# UCC.net
KiCad netlist of a schematic drawn in EasyEDA Pro
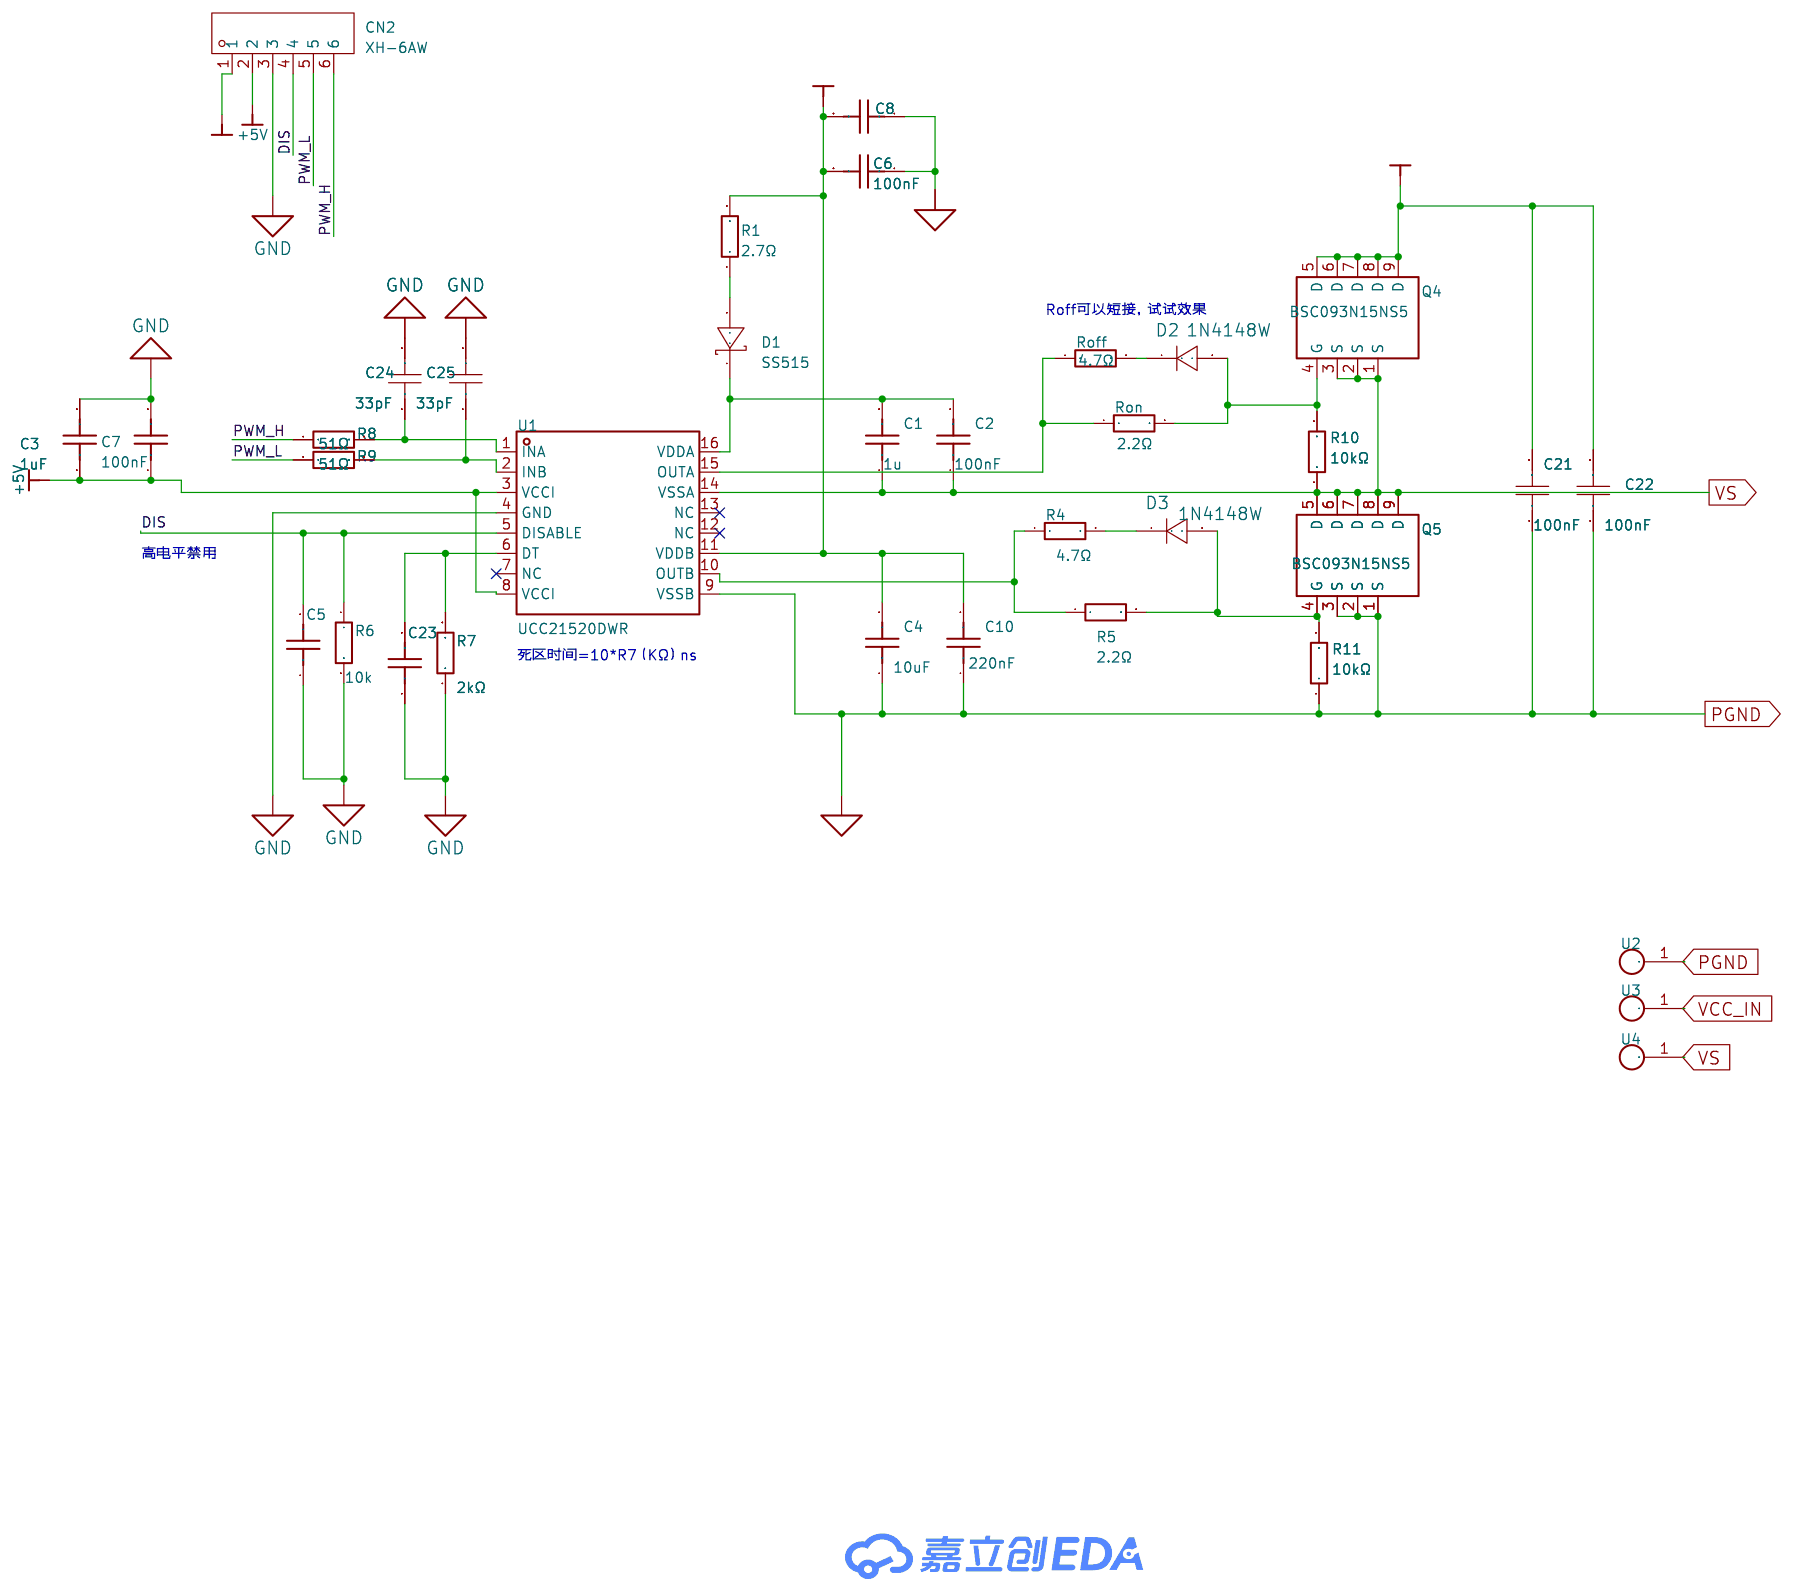
[diagram p0: schematic sheet]

(export (version "E")
  (design (tool "Eeschema 10.0.6"))
  (components
    (comp (ref "C1")
      (value "1u")
      (footprint "easyedapro:C0805")
      (libsource (lib "easyedapro") (part "Capacitance"))
    )
    (comp (ref "C2")
      (value "100nF")
      (footprint "easyedapro:C0805")
      (libsource (lib "easyedapro") (part "Capacitance"))
    )
    (comp (ref "C3")
      (value "1uF")
      (fields
        (field (name "Manufacturer Part") "CC0603KRX7R9BB104")
        (field (name "Manufacturer") "YAGEO(国巨)")
      )
      (libsource (lib "easyedapro") (part "CapAcitance"))
    )
    (comp (ref "C4")
      (value "10uF")
      (fields
        (field (name "Manufacturer Part") "CL10A105KB8NNNC")
        (field (name "Manufacturer") "SAMSUNG(三星)")
      )
      (libsource (lib "easyedapro") (part "CapAcitance"))
    )
    (comp (ref "C5")
      (value "1nF")
      (fields
        (field (name "Manufacturer Part") "CL10B102KB8NNNC")
        (field (name "Manufacturer") "SAMSUNG(三星)")
      )
      (libsource (lib "easyedapro") (part "CapAcitance"))
    )
    (comp (ref "C6")
      (value "100nF")
      (description "容值:1uF;精度:±10%;额定电压:50V;温度系数:X5R;")
      (libsource (lib "easyedapro") (part "CapAcitance"))
    )
    (comp (ref "C7")
      (value "100nF")
      (fields
        (field (name "Manufacturer Part") "CL10A105KB8NNNC")
        (field (name "Manufacturer") "SAMSUNG(三星)")
      )
      (libsource (lib "easyedapro") (part "CapAcitance"))
    )
    (comp (ref "C8")
      (value "10uF")
      (description "容值:10uF;精度:±10%;额定电压:10V;温度系数:X5R;")
      (libsource (lib "easyedapro") (part "CapAcitance"))
    )
    (comp (ref "C10")
      (value "220nF")
      (fields
        (field (name "Manufacturer Part") "CC0603KRX7R9BB104")
        (field (name "Manufacturer") "YAGEO(国巨)")
      )
      (libsource (lib "easyedapro") (part "CapAcitance"))
    )
    (comp (ref "C21")
      (value "100nF")
      (footprint "easyedapro:C1206")
      (description "容值:4.7uF;精度:±10%;额定电压:50V;温度系数:X7R;")
      (fields (field (name "Manufacturer Part") "AM06B475K500NT") (field (name "Manufacturer") "FH(风华)"))
      (libsource (lib "easyedapro") (part "AM06B475K500NT"))
    )
    (comp (ref "C22")
      (value "100nF")
      (footprint "easyedapro:C1206")
      (description "容值:4.7uF;精度:±10%;额定电压:50V;温度系数:X7R;")
      (fields (field (name "Manufacturer Part") "AM06B475K500NT") (field (name "Manufacturer") "FH(风华)"))
      (libsource (lib "easyedapro") (part "AM06B475K500NT"))
    )
    (comp (ref "C23")
      (value "1nF")
      (fields
        (field (name "Manufacturer Part") "CL10B102KB8NNNC")
        (field (name "Manufacturer") "SAMSUNG(三星)")
      )
      (libsource (lib "easyedapro") (part "CapAcitance"))
    )
    (comp (ref "C24")
      (value "33pF")
      (fields
        (field (name "Manufacturer Part") "CC0603JRNPO9BN330")
        (field (name "Manufacturer") "YAGEO(国巨)")
      )
      (libsource (lib "easyedapro") (part "CapAcitance"))
    )
    (comp (ref "C25")
      (value "33pF")
      (fields
        (field (name "Manufacturer Part") "CC0603JRNPO9BN330")
        (field (name "Manufacturer") "YAGEO(国巨)")
      )
      (libsource (lib "easyedapro") (part "CapAcitance"))
    )
    (comp (ref "CN2")
      (value "XH-6AW")
      (footprint "easyedapro:CONN-TH_6P-P2.54_HCTL_XH-6AW_C2908615")
      (fields (field (name "Manufacturer") "HCTL(华灿天禄)"))
      (libsource (lib "easyedapro") (part "XH-6AW_C2908615"))
    )
    (comp (ref "D1")
      (value "SS515")
      (footprint "easyedapro:SMA_L4.3-W2.6-LS5.2-RD")
      (description "100V,5A,VF=0.85V@5A")
      (fields (field (name "Manufacturer") "MDD"))
      (libsource (lib "easyedapro") (part "SS510_C65010"))
    )
    (comp (ref "D2")
      (value "1N4148W")
      (fields (field (name "Manufacturer") "CJ(江苏长电/长晶)"))
      (libsource (lib "easyedapro") (part "1N4148W"))
    )
    (comp (ref "D3")
      (value "1N4148W")
      (fields (field (name "Manufacturer") "CJ(江苏长电/长晶)"))
      (libsource (lib "easyedapro") (part "1N4148W"))
    )
    (comp (ref "Q4")
      (value "BSC093N15NS5")
      (footprint "easyedapro:PG-TDSON-8_L5.0-W6.0-P1.27-LS6.2-BL-EP")
      (fields (field (name "Manufacturer") "Infineon(英飞凌)"))
      (libsource (lib "easyedapro") (part "BSC093N15NS5"))
    )
    (comp (ref "Q5")
      (value "BSC093N15NS5")
      (footprint "easyedapro:PG-TDSON-8_L5.0-W6.0-P1.27-LS6.2-BL-EP")
      (fields (field (name "Manufacturer") "Infineon(英飞凌)"))
      (libsource (lib "easyedapro") (part "BSC093N15NS5"))
    )
    (comp (ref "R1")
      (value "2.7Ω")
      (footprint "easyedapro:R1206")
      (fields (field (name "Manufacturer Part") "RC0805FR-072R2L") (field (name "Manufacturer") "YAGEO(国巨)"))
      (libsource (lib "easyedapro") (part "电阻_1"))
    )
    (comp (ref "R4")
      (value "4.7Ω")
      (footprint "easyedapro:R1206")
      (libsource (lib "easyedapro") (part "电阻_1"))
    )
    (comp (ref "R5")
      (value "2.2Ω")
      (footprint "easyedapro:R1206")
      (libsource (lib "easyedapro") (part "电阻_1"))
    )
    (comp (ref "R6")
      (value "10k")
      (footprint "easyedapro:R1206")
      (fields (field (name "Manufacturer Part") "RC0603FR-0710KL") (field (name "Manufacturer") "YAGEO(国巨)"))
      (libsource (lib "easyedapro") (part "电阻_1"))
    )
    (comp (ref "R7")
      (value "2kΩ")
      (footprint "easyedapro:R1206")
      (fields (field (name "Manufacturer Part") "RC0603FR-0710KL") (field (name "Manufacturer") "YAGEO(国巨)"))
      (libsource (lib "easyedapro") (part "电阻_1"))
    )
    (comp (ref "R8")
      (value "51Ω")
      (footprint "easyedapro:R1206")
      (fields
        (field (name "Manufacturer Part") "0603WAF510JT5E")
        (field (name "Manufacturer") "UNI-ROYAL(厚声)")
      )
      (libsource (lib "easyedapro") (part "电阻_1"))
    )
    (comp (ref "R9")
      (value "51Ω")
      (footprint "easyedapro:R1206")
      (fields
        (field (name "Manufacturer Part") "0603WAF510JT5E")
        (field (name "Manufacturer") "UNI-ROYAL(厚声)")
      )
      (libsource (lib "easyedapro") (part "电阻_1"))
    )
    (comp (ref "R10")
      (value "10kΩ")
      (footprint "easyedapro:R1206")
      (fields
        (field (name "Manufacturer Part") "0603WAF1002T5E")
        (field (name "Manufacturer") "UNI-ROYAL(厚声)")
      )
      (libsource (lib "easyedapro") (part "电阻_1"))
    )
    (comp (ref "R11")
      (value "10kΩ")
      (footprint "easyedapro:R1206")
      (fields
        (field (name "Manufacturer Part") "0603WAF1002T5E")
        (field (name "Manufacturer") "UNI-ROYAL(厚声)")
      )
      (libsource (lib "easyedapro") (part "电阻_1"))
    )
    (comp (ref "Roff")
      (value "4.7Ω")
      (footprint "easyedapro:R1206")
      (libsource (lib "easyedapro") (part "电阻_1"))
    )
    (comp (ref "Ron")
      (value "2.2Ω")
      (footprint "easyedapro:R1206")
      (libsource (lib "easyedapro") (part "电阻_1"))
    )
    (comp (ref "U1")
      (value "UCC21520DWR")
      (footprint "easyedapro:SOIC-16_L10.3-W7.5-P1.27-LS10.3-BL")
      (fields (field (name "Manufacturer") "TI(德州仪器)"))
      (libsource (lib "easyedapro") (part "UCC21520DWR"))
    )
    (comp (ref "U2")
      (value "~")
      (footprint "easyedapro:3.5mm香蕉头")
      (libsource (lib "easyedapro") (part "3.5mm香蕉头"))
    )
    (comp (ref "U3")
      (value "~")
      (footprint "easyedapro:3.5mm香蕉头")
      (libsource (lib "easyedapro") (part "3.5mm香蕉头"))
    )
    (comp (ref "U4")
      (value "~")
      (footprint "easyedapro:3.5mm香蕉头")
      (libsource (lib "easyedapro") (part "3.5mm香蕉头"))
    )
  )
  (nets
    (net (code "1") (name "+5V") (class "Default")
      (node (ref "C3") (pin "1") (pinfunction "1_1") (pintype "input"))
      (node (ref "C7") (pin "1") (pinfunction "1_1") (pintype "input"))
      (node (ref "CN2") (pin "2") (pinfunction "2_2") (pintype "unspecified"))
      (node (ref "U1") (pin "3") (pinfunction "VCCI_3") (pintype "input"))
      (node (ref "U1") (pin "8") (pinfunction "VCCI_8") (pintype "input"))
    )
    (net (code "2") (name "+12V") (class "Default")
      (node (ref "C10") (pin "2") (pinfunction "2_2") (pintype "input"))
      (node (ref "C4") (pin "2") (pinfunction "2_2") (pintype "input"))
      (node (ref "C6") (pin "2") (pinfunction "2_2") (pintype "input"))
      (node (ref "C8") (pin "2") (pinfunction "2_2") (pintype "input"))
      (node (ref "CN2") (pin "1") (pinfunction "1_1") (pintype "unspecified"))
      (node (ref "R1") (pin "2") (pinfunction "2_2") (pintype "input"))
      (node (ref "U1") (pin "11") (pinfunction "VDDB_11") (pintype "input"))
    )
    (net (code "3") (name "/DIS") (class "Default")
      (node (ref "C5") (pin "2") (pinfunction "2_2") (pintype "input"))
      (node (ref "CN2") (pin "4") (pinfunction "4_4") (pintype "unspecified"))
      (node (ref "R6") (pin "1") (pinfunction "1_1") (pintype "input"))
      (node (ref "U1") (pin "5") (pinfunction "DISABLE_5") (pintype "input"))
    )
    (net (code "4") (name "/PWM_H") (class "Default")
      (node (ref "CN2") (pin "6") (pinfunction "6_6") (pintype "unspecified"))
      (node (ref "R8") (pin "1") (pinfunction "1_1") (pintype "input"))
    )
    (net (code "5") (name "/PWM_L") (class "Default")
      (node (ref "CN2") (pin "5") (pinfunction "5_5") (pintype "unspecified"))
      (node (ref "R9") (pin "1") (pinfunction "1_1") (pintype "input"))
    )
    (net (code "6") (name "GND") (class "Default")
      (node (ref "C23") (pin "1") (pinfunction "1_1") (pintype "input"))
      (node (ref "C24") (pin "2") (pinfunction "2_2") (pintype "input"))
      (node (ref "C25") (pin "2") (pinfunction "2_2") (pintype "input"))
      (node (ref "C3") (pin "2") (pinfunction "2_2") (pintype "input"))
      (node (ref "C5") (pin "1") (pinfunction "1_1") (pintype "input"))
      (node (ref "C7") (pin "2") (pinfunction "2_2") (pintype "input"))
      (node (ref "CN2") (pin "3") (pinfunction "3_3") (pintype "unspecified"))
      (node (ref "R6") (pin "2") (pinfunction "2_2") (pintype "input"))
      (node (ref "R7") (pin "1") (pinfunction "1_1") (pintype "input"))
      (node (ref "U1") (pin "4") (pinfunction "GND_4") (pintype "input"))
    )
    (net (code "7") (name "Net-(D1-A)") (class "Default")
      (node (ref "D1") (pin "2") (pinfunction "A_2") (pintype "input"))
      (node (ref "R1") (pin "1") (pinfunction "1_1") (pintype "input"))
    )
    (net (code "8") (name "Net-(D1-K)") (class "Default")
      (node (ref "C1") (pin "2") (pinfunction "2_2") (pintype "input"))
      (node (ref "C2") (pin "2") (pinfunction "2_2") (pintype "input"))
      (node (ref "D1") (pin "1") (pinfunction "K_1") (pintype "input"))
      (node (ref "U1") (pin "16") (pinfunction "VDDA_16") (pintype "input"))
    )
    (net (code "9") (name "Net-(D2-A)") (class "Default")
      (node (ref "D2") (pin "2") (pinfunction "A_2") (pintype "input"))
      (node (ref "Q4") (pin "4") (pinfunction "G_4") (pintype "unspecified"))
      (node (ref "R10") (pin "2") (pinfunction "2_2") (pintype "input"))
      (node (ref "Ron") (pin "2") (pinfunction "2_2") (pintype "input"))
    )
    (net (code "10") (name "Net-(D2-K)") (class "Default")
      (node (ref "D2") (pin "1") (pinfunction "K_1") (pintype "input"))
      (node (ref "Roff") (pin "2") (pinfunction "2_2") (pintype "input"))
    )
    (net (code "11") (name "Net-(D3-A)") (class "Default")
      (node (ref "D3") (pin "2") (pinfunction "A_2") (pintype "input"))
      (node (ref "Q5") (pin "4") (pinfunction "G_4") (pintype "unspecified"))
      (node (ref "R11") (pin "2") (pinfunction "2_2") (pintype "input"))
      (node (ref "R5") (pin "2") (pinfunction "2_2") (pintype "input"))
    )
    (net (code "12") (name "Net-(D3-K)") (class "Default")
      (node (ref "D3") (pin "1") (pinfunction "K_1") (pintype "input"))
      (node (ref "R4") (pin "2") (pinfunction "2_2") (pintype "input"))
    )
    (net (code "13") (name "Net-(U1-DT)") (class "Default")
      (node (ref "C23") (pin "2") (pinfunction "2_2") (pintype "input"))
      (node (ref "R7") (pin "2") (pinfunction "2_2") (pintype "input"))
      (node (ref "U1") (pin "6") (pinfunction "DT_6") (pintype "input"))
    )
    (net (code "14") (name "Net-(U1-INA)") (class "Default")
      (node (ref "C24") (pin "1") (pinfunction "1_1") (pintype "input"))
      (node (ref "R8") (pin "2") (pinfunction "2_2") (pintype "input"))
      (node (ref "U1") (pin "1") (pinfunction "INA_1") (pintype "input"))
    )
    (net (code "15") (name "Net-(U1-INB)") (class "Default")
      (node (ref "C25") (pin "1") (pinfunction "1_1") (pintype "input"))
      (node (ref "R9") (pin "2") (pinfunction "2_2") (pintype "input"))
      (node (ref "U1") (pin "2") (pinfunction "INB_2") (pintype "input"))
    )
    (net (code "16") (name "Net-(U1-OUTA)") (class "Default")
      (node (ref "Roff") (pin "1") (pinfunction "1_1") (pintype "input"))
      (node (ref "Ron") (pin "1") (pinfunction "1_1") (pintype "input"))
      (node (ref "U1") (pin "15") (pinfunction "OUTA_15") (pintype "input"))
    )
    (net (code "17") (name "Net-(U1-OUTB)") (class "Default")
      (node (ref "R4") (pin "1") (pinfunction "1_1") (pintype "input"))
      (node (ref "R5") (pin "1") (pinfunction "1_1") (pintype "input"))
      (node (ref "U1") (pin "10") (pinfunction "OUTB_10") (pintype "input"))
    )
    (net (code "18") (name "PGND") (class "Default")
      (node (ref "C10") (pin "1") (pinfunction "1_1") (pintype "input"))
      (node (ref "C21") (pin "1") (pinfunction "1_1") (pintype "unspecified"))
      (node (ref "C22") (pin "1") (pinfunction "1_1") (pintype "unspecified"))
      (node (ref "C4") (pin "1") (pinfunction "1_1") (pintype "input"))
      (node (ref "C6") (pin "1") (pinfunction "1_1") (pintype "input"))
      (node (ref "C8") (pin "1") (pinfunction "1_1") (pintype "input"))
      (node (ref "Q5") (pin "1") (pinfunction "S_1") (pintype "unspecified"))
      (node (ref "Q5") (pin "2") (pinfunction "S_2") (pintype "unspecified"))
      (node (ref "Q5") (pin "3") (pinfunction "S_3") (pintype "unspecified"))
      (node (ref "R11") (pin "1") (pinfunction "1_1") (pintype "input"))
      (node (ref "U1") (pin "9") (pinfunction "VSSB_9") (pintype "input"))
      (node (ref "U2") (pin "1") (pinfunction "1_1") (pintype "input"))
    )
    (net (code "19") (name "VCC_IN") (class "Default")
      (node (ref "C21") (pin "2") (pinfunction "2_2") (pintype "unspecified"))
      (node (ref "C22") (pin "2") (pinfunction "2_2") (pintype "unspecified"))
      (node (ref "Q4") (pin "5") (pinfunction "D_5") (pintype "unspecified"))
      (node (ref "Q4") (pin "6") (pinfunction "D_6") (pintype "unspecified"))
      (node (ref "Q4") (pin "7") (pinfunction "D_7") (pintype "unspecified"))
      (node (ref "Q4") (pin "8") (pinfunction "D_8") (pintype "unspecified"))
      (node (ref "Q4") (pin "9") (pinfunction "D_9") (pintype "unspecified"))
      (node (ref "U3") (pin "1") (pinfunction "1_1") (pintype "input"))
    )
    (net (code "20") (name "VS") (class "Default")
      (node (ref "C1") (pin "1") (pinfunction "1_1") (pintype "input"))
      (node (ref "C2") (pin "1") (pinfunction "1_1") (pintype "input"))
      (node (ref "Q4") (pin "1") (pinfunction "S_1") (pintype "unspecified"))
      (node (ref "Q4") (pin "2") (pinfunction "S_2") (pintype "unspecified"))
      (node (ref "Q4") (pin "3") (pinfunction "S_3") (pintype "unspecified"))
      (node (ref "Q5") (pin "5") (pinfunction "D_5") (pintype "unspecified"))
      (node (ref "Q5") (pin "6") (pinfunction "D_6") (pintype "unspecified"))
      (node (ref "Q5") (pin "7") (pinfunction "D_7") (pintype "unspecified"))
      (node (ref "Q5") (pin "8") (pinfunction "D_8") (pintype "unspecified"))
      (node (ref "Q5") (pin "9") (pinfunction "D_9") (pintype "unspecified"))
      (node (ref "R10") (pin "1") (pinfunction "1_1") (pintype "input"))
      (node (ref "U1") (pin "14") (pinfunction "VSSA_14") (pintype "input"))
      (node (ref "U4") (pin "1") (pinfunction "1_1") (pintype "input"))
    )
    (net (code "21") (name "unconnected-(U1-NC-Pad7)") (class "Default")
      (node (ref "U1") (pin "7") (pinfunction "NC_7") (pintype "input+no_connect"))
    )
    (net (code "22") (name "unconnected-(U1-NC-Pad12)") (class "Default")
      (node (ref "U1") (pin "12") (pinfunction "NC_12") (pintype "input+no_connect"))
    )
    (net (code "23") (name "unconnected-(U1-NC-Pad13)") (class "Default")
      (node (ref "U1") (pin "13") (pinfunction "NC_13") (pintype "input+no_connect"))
    )
  )
)
